# V1.net
KiCad netlist of a schematic drawn in EAGLE
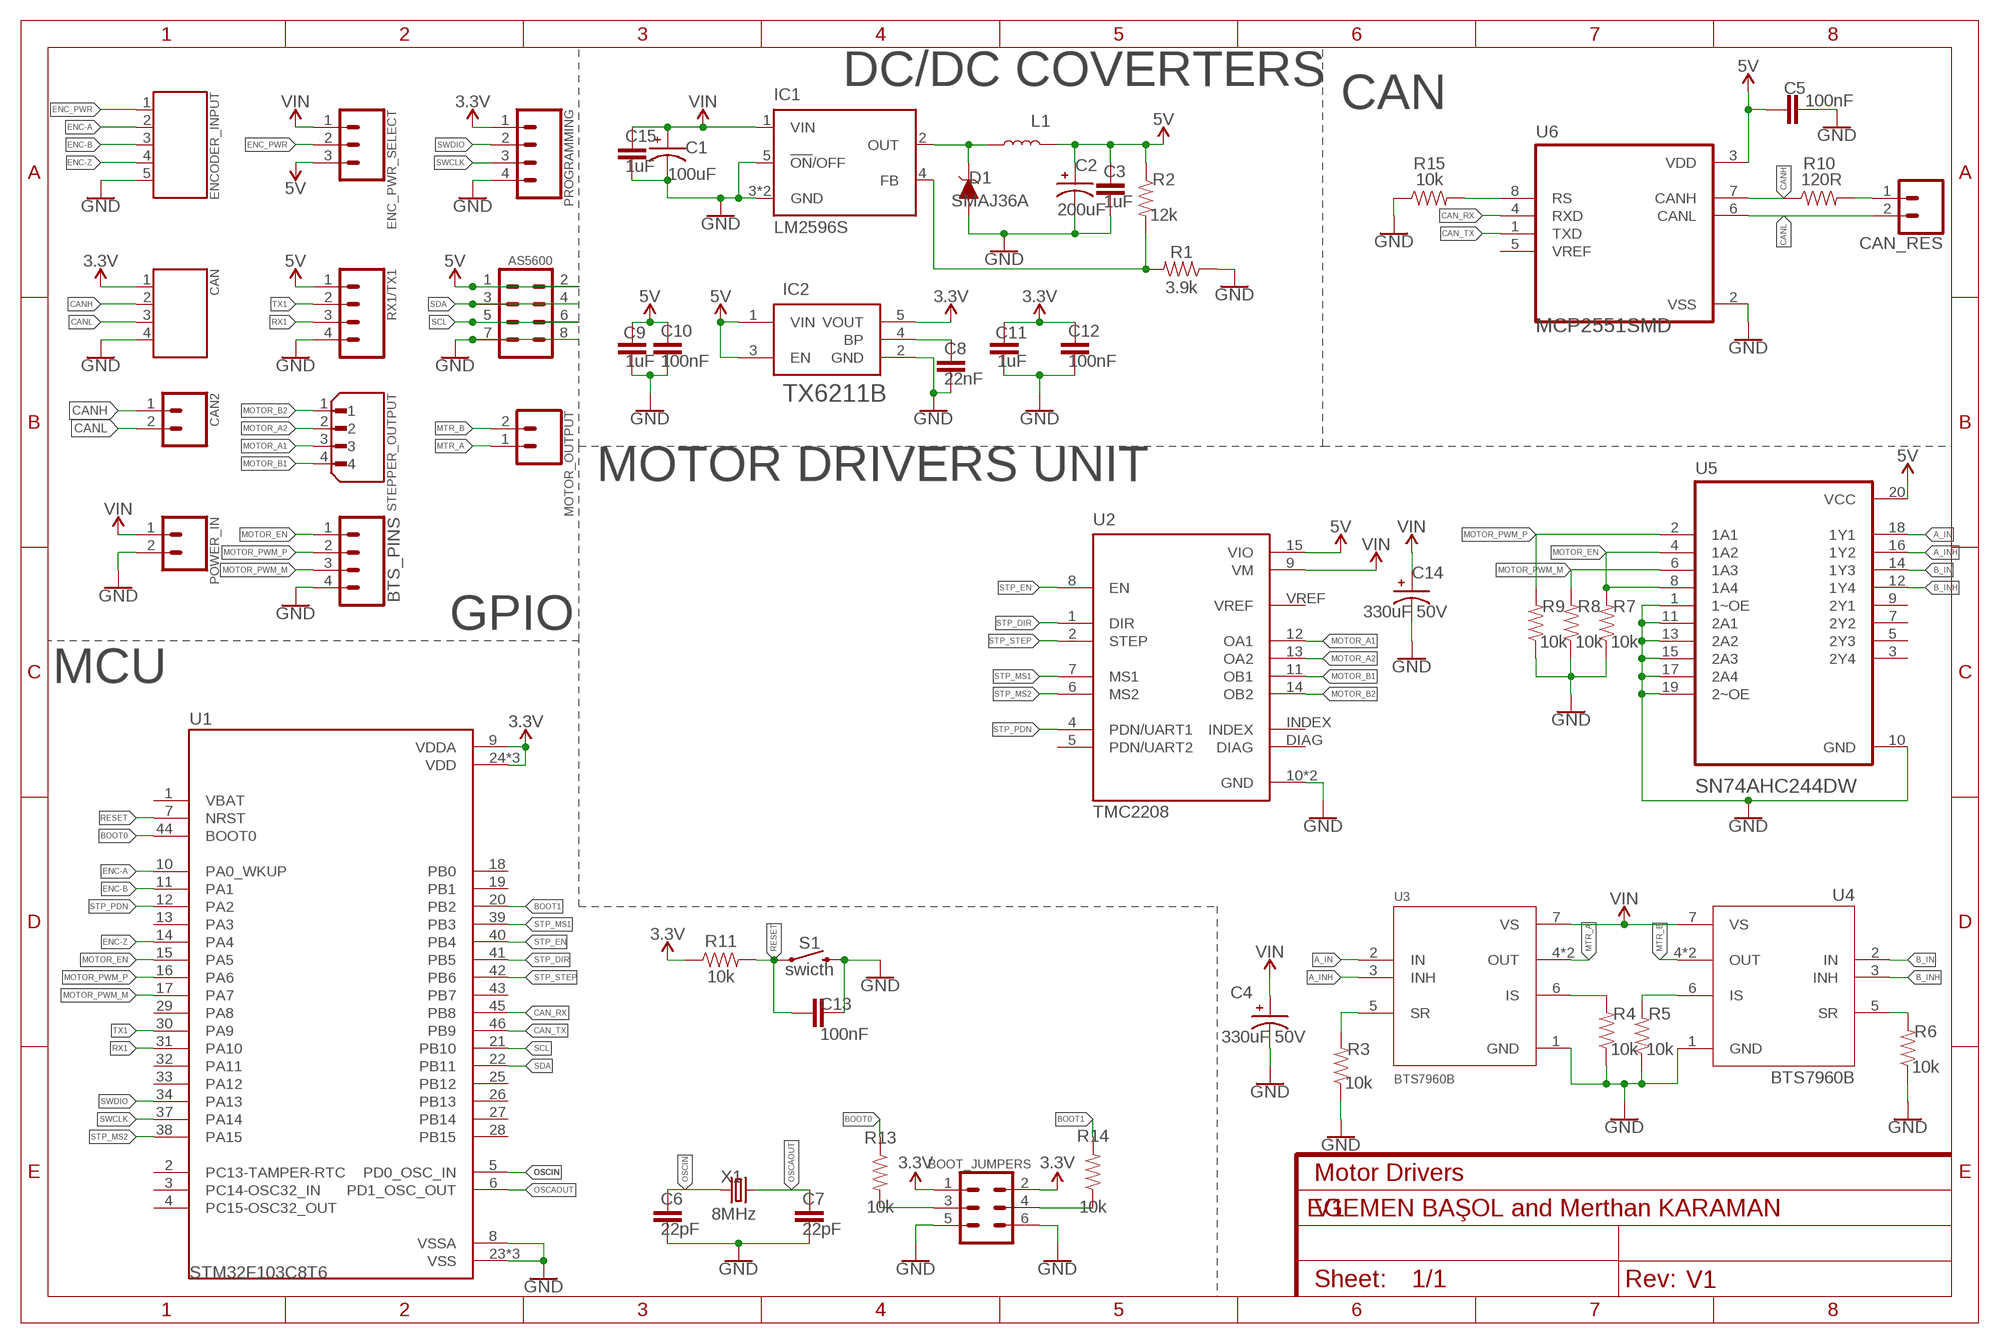
[diagram p0: schematic, sheet 1]

(export (version "E")
  (design (tool "Eeschema 10.0.6"))
  (components
    (comp (ref "AS5600")
      (value "5V/SDA/SCL/GND")
      (footprint "eagle-import:2X4")
      (libsource (lib "eagle-import") (part "CONN_04X2"))
    )
    (comp (ref "BOOT_JUMPERS")
      (value "CONN_03X2FEMALE")
      (footprint "eagle-import:2X3")
      (libsource (lib "eagle-import") (part "CONN_03X2FEMALE"))
    )
    (comp (ref "BTS_PINS")
      (value "GND/ PWM_M/ PWM_P/ EN")
      (footprint "eagle-import:1X04")
      (libsource (lib "eagle-import") (part "CONN_04"))
    )
    (comp (ref "C1")
      (value "100uF")
      (footprint "eagle-import:CPOL-SMD")
      (fields (field (name "MF") "Panasonic") (field (name "MP") "EEEFN1H101L"))
      (libsource (lib "eagle-import") (part "CPOL-SMD"))
    )
    (comp (ref "C2")
      (value "200uF")
      (footprint "eagle-import:CPOL-SMD")
      (fields (field (name "MF") "Panasonic") (field (name "MP") "EEEFN1H101L"))
      (libsource (lib "eagle-import") (part "CPOL-SMD"))
    )
    (comp (ref "C3")
      (value "1uF")
      (footprint "eagle-import:0603")
      (libsource (lib "eagle-import") (part "0.18UF-0603-10V-10%"))
    )
    (comp (ref "C4")
      (value "330uF 50V")
      (footprint "eagle-import:CPOL-RADIAL-5MM-10MM")
      (fields (field (name "MF") "Panasonic") (field (name "MP") "ECA2VM4R7"))
      (libsource (lib "eagle-import") (part "CPOL-RADIAL-5MM-10MM"))
    )
    (comp (ref "C5")
      (value "100nF")
      (footprint "eagle-import:0805")
      (libsource (lib "eagle-import") (part "CAP-0805"))
    )
    (comp (ref "C6")
      (value "22pF")
      (footprint "eagle-import:0805")
      (libsource (lib "eagle-import") (part "2.2UF-0805-25V-(+80/-20%)"))
    )
    (comp (ref "C7")
      (value "22pF")
      (footprint "eagle-import:0805")
      (libsource (lib "eagle-import") (part "2.2UF-0805-25V-(+80/-20%)"))
    )
    (comp (ref "C8")
      (value "22nF")
      (footprint "eagle-import:0805")
      (libsource (lib "eagle-import") (part "2.2UF-0805-25V-(+80/-20%)"))
    )
    (comp (ref "C9")
      (value "1uF")
      (footprint "eagle-import:0805")
      (libsource (lib "eagle-import") (part "CAP-0805"))
    )
    (comp (ref "C10")
      (value "100nF")
      (footprint "eagle-import:0805")
      (libsource (lib "eagle-import") (part "2.2UF-0805-25V-(+80/-20%)"))
    )
    (comp (ref "C11")
      (value "1uF")
      (footprint "eagle-import:0805")
      (libsource (lib "eagle-import") (part "CAP-0805"))
    )
    (comp (ref "C12")
      (value "100nF")
      (footprint "eagle-import:0805")
      (libsource (lib "eagle-import") (part "2.2UF-0805-25V-(+80/-20%)"))
    )
    (comp (ref "C13")
      (value "100nF")
      (footprint "eagle-import:0805")
      (libsource (lib "eagle-import") (part "2.2UF-0805-25V-(+80/-20%)"))
    )
    (comp (ref "C14")
      (value "330uF 50V")
      (footprint "eagle-import:CPOL-RADIAL-5MM-10MM")
      (fields (field (name "MF") "Panasonic") (field (name "MP") "ECA2VM4R7"))
      (libsource (lib "eagle-import") (part "CPOL-RADIAL-5MM-10MM"))
    )
    (comp (ref "C15")
      (value "1uF")
      (footprint "eagle-import:0805")
      (libsource (lib "eagle-import") (part "2.2UF-0805-25V-(+80/-20%)"))
    )
    (comp (ref "CAN")
      (value "3.3V/CANH/CANL/GND")
      (footprint "eagle-import:5.08MM_4PIN")
      (fields (field (name "MF") "CUI Devices") (field (name "MP") "TB006-508-04BE"))
      (libsource (lib "eagle-import") (part "5.08MM_4PIN"))
    )
    (comp (ref "CAN2")
      (value "CANH/CANL")
      (footprint "eagle-import:5.08MM_2PIN")
      (libsource (lib "eagle-import") (part "5.08MM_2PIN"))
    )
    (comp (ref "CAN_RES")
      (value "CONN_02")
      (footprint "eagle-import:1X02")
      (libsource (lib "eagle-import") (part "CONN_02"))
    )
    (comp (ref "D1")
      (value "SMAJ36A")
      (footprint "eagle-import:DO-214AC")
      (libsource (lib "eagle-import") (part "DIODE_TVS_UNI"))
    )
    (comp (ref "ENCODER_INPUT")
      (value "PWR/A/B/Z/GND")
      (footprint "eagle-import:5.08MM_5PIN")
      (fields (field (name "MF") "CUI Devices") (field (name "MP") "TB006-508-05BE"))
      (libsource (lib "eagle-import") (part "5.08MM_5PIN"))
    )
    (comp (ref "ENC_PWR_SELECT")
      (value "VIN/PWR/5V")
      (footprint "eagle-import:1X03")
      (libsource (lib "eagle-import") (part "CONN_03"))
    )
    (comp (ref "IC1")
      (value "LM2596S")
      (footprint "eagle-import:TO263-5")
      (libsource (lib "eagle-import") (part "LM2596S"))
    )
    (comp (ref "IC2")
      (value "TX6211B")
      (footprint "eagle-import:SOT23-5")
      (libsource (lib "eagle-import") (part "TX6211B"))
    )
    (comp (ref "L1")
      (value "47uH")
      (footprint "eagle-import:COIL_14X14")
      (libsource (lib "eagle-import") (part "COIL"))
    )
    (comp (ref "MOTOR_OUTPUT")
      (value "5.08MM_2PIN")
      (footprint "eagle-import:5.08MM_2PIN")
      (libsource (lib "eagle-import") (part "5.08MM_2PIN"))
    )
    (comp (ref "POWER_IN")
      (value "VIN/GND")
      (footprint "eagle-import:5.08MM_2PIN")
      (libsource (lib "eagle-import") (part "5.08MM_2PIN"))
    )
    (comp (ref "PROGRAMMING")
      (value "3.3V/SWDIO/SWCLK/GND")
      (footprint "eagle-import:1X04")
      (libsource (lib "eagle-import") (part "CONN_04"))
    )
    (comp (ref "R1")
      (value "3.9k")
      (footprint "eagle-import:0805")
      (libsource (lib "eagle-import") (part "RESISTOR0805"))
    )
    (comp (ref "R2")
      (value "12k")
      (footprint "eagle-import:0805")
      (libsource (lib "eagle-import") (part "RESISTOR0805"))
    )
    (comp (ref "R3")
      (value "10k")
      (footprint "eagle-import:0805")
      (libsource (lib "eagle-import") (part "RESISTOR0805"))
    )
    (comp (ref "R4")
      (value "10k")
      (footprint "eagle-import:0805")
      (libsource (lib "eagle-import") (part "RESISTOR0805"))
    )
    (comp (ref "R5")
      (value "10k")
      (footprint "eagle-import:0805")
      (libsource (lib "eagle-import") (part "RESISTOR0805"))
    )
    (comp (ref "R6")
      (value "10k")
      (footprint "eagle-import:0805")
      (libsource (lib "eagle-import") (part "RESISTOR0805"))
    )
    (comp (ref "R7")
      (value "10k")
      (footprint "eagle-import:0805")
      (libsource (lib "eagle-import") (part "RESISTOR0805"))
    )
    (comp (ref "R8")
      (value "10k")
      (footprint "eagle-import:0805")
      (libsource (lib "eagle-import") (part "RESISTOR0805"))
    )
    (comp (ref "R9")
      (value "10k")
      (footprint "eagle-import:0805")
      (libsource (lib "eagle-import") (part "RESISTOR0805"))
    )
    (comp (ref "R10")
      (value "120R")
      (footprint "eagle-import:0805")
      (libsource (lib "eagle-import") (part "RESISTOR0805"))
    )
    (comp (ref "R11")
      (value "10k")
      (footprint "eagle-import:0805")
      (libsource (lib "eagle-import") (part "SparkFun-Resistors_532_RESISTOR0805"))
    )
    (comp (ref "R13")
      (value "10k")
      (footprint "eagle-import:0805")
      (libsource (lib "eagle-import") (part "SparkFun-Resistors_532_RESISTOR0805"))
    )
    (comp (ref "R14")
      (value "10k")
      (footprint "eagle-import:0805")
      (libsource (lib "eagle-import") (part "SparkFun-Resistors_532_RESISTOR0805"))
    )
    (comp (ref "R15")
      (value "10k")
      (footprint "eagle-import:0805")
      (libsource (lib "eagle-import") (part "RESISTOR0805"))
    )
    (comp (ref "RX1/TX1")
      (value "5V/TX1/RX1/GND")
      (footprint "eagle-import:1X04")
      (libsource (lib "eagle-import") (part "CONN_04"))
    )
    (comp (ref "S1")
      (value "swicth")
      (footprint "eagle-import:TACTILE_SWITCH_SMD_5.2MM")
      (libsource (lib "eagle-import") (part "MOMENTARY-SWITCH-SPST-SMD-5.2MM-TALL"))
    )
    (comp (ref "STEPPER_OUTPUT")
      (value "4PIN_TUNIC_2.5MM")
      (footprint "eagle-import:JST_B4B-XH-A(LF)(SN)")
      (fields (field (name "MF") "JST Sales") (field (name "MP") "B4B-XH-A(LF)(SN)"))
      (libsource (lib "eagle-import") (part "4PIN_TUNIC_2.5MM"))
    )
    (comp (ref "U1")
      (value "STM32F103C8T6")
      (footprint "eagle-import:LQFP-48")
      (fields (field (name "MF") "STMicroelectronics"))
      (libsource (lib "eagle-import") (part "STM32F103C8T6"))
    )
    (comp (ref "U2")
      (value "TMC2208")
      (footprint "eagle-import:MODULE_TMC2208_SILENTSTEPSTICK")
      (fields (field (name "MF") "Trinamic Motion") (field (name "MP") "TMC2208 SILENTSTEPSTICK"))
      (libsource (lib "eagle-import") (part "TMC2208_SILENTSTEPSTICK"))
    )
    (comp (ref "U3")
      (value "BTS7960B")
      (footprint "eagle-import:DPAK127P1490X440-8N")
      (libsource (lib "eagle-import") (part "BTS7960B"))
    )
    (comp (ref "U4")
      (value "BTS7960B")
      (footprint "eagle-import:DPAK127P1490X440-8N")
      (libsource (lib "eagle-import") (part "BTS7960B"))
    )
    (comp (ref "U5")
      (value "SN74AHC244DW")
      (footprint "eagle-import:SOIC127P1030X265-20N")
      (fields (field (name "MF") "Texas Instruments"))
      (libsource (lib "eagle-import") (part "SN74AHC244DW"))
    )
    (comp (ref "U6")
      (value "MCP2551SMD")
      (footprint "eagle-import:SOIC-8")
      (libsource (lib "eagle-import") (part "MCP2551SMD"))
    )
    (comp (ref "X1")
      (value "8MHz")
      (footprint "eagle-import:HC49")
      (libsource (lib "eagle-import") (part "CRYSTALS-NOGND-HC49"))
    )
  )
  (nets
    (net (code "1") (name "3.3V") (class "Default")
      (node (ref "BOOT_JUMPERS") (pin "1") (pinfunction "1_1") (pintype "bidirectional"))
      (node (ref "BOOT_JUMPERS") (pin "2") (pinfunction "2_2") (pintype "bidirectional"))
      (node (ref "C11") (pin "2") (pinfunction "2_2") (pintype "passive"))
      (node (ref "C12") (pin "2") (pinfunction "2_2") (pintype "passive"))
      (node (ref "CAN") (pin "1") (pinfunction "1_1") (pintype "passive"))
      (node (ref "IC2") (pin "5") (pinfunction "VOUT_5") (pintype "output"))
      (node (ref "PROGRAMMING") (pin "1") (pinfunction "1_1") (pintype "passive"))
      (node (ref "R11") (pin "1") (pinfunction "1_1") (pintype "passive"))
      (node (ref "U1") (pin "24") (pinfunction "VDD_24") (pintype "power_in"))
      (node (ref "U1") (pin "36") (pinfunction "VDD_36") (pintype "power_in"))
      (node (ref "U1") (pin "48") (pinfunction "VDD_48") (pintype "power_in"))
      (node (ref "U1") (pin "9") (pinfunction "VDDA_9") (pintype "power_in"))
    )
    (net (code "2") (name "5V") (class "Default")
      (node (ref "AS5600") (pin "1") (pinfunction "1_1") (pintype "passive"))
      (node (ref "AS5600") (pin "2") (pinfunction "2_2") (pintype "passive"))
      (node (ref "C10") (pin "2") (pinfunction "2_2") (pintype "passive"))
      (node (ref "C2") (pin "1") (pinfunction "1_1") (pintype "passive"))
      (node (ref "C3") (pin "2") (pinfunction "2_2") (pintype "passive"))
      (node (ref "C5") (pin "2") (pinfunction "2_2") (pintype "passive"))
      (node (ref "C9") (pin "2") (pinfunction "2_2") (pintype "passive"))
      (node (ref "ENC_PWR_SELECT") (pin "3") (pinfunction "3_3") (pintype "passive"))
      (node (ref "IC2") (pin "1") (pinfunction "VIN_1") (pintype "input"))
      (node (ref "IC2") (pin "3") (pinfunction "EN_3") (pintype "input"))
      (node (ref "L1") (pin "P$2") (pinfunction "2_P$2") (pintype "passive"))
      (node (ref "R2") (pin "1") (pinfunction "1_1") (pintype "passive"))
      (node (ref "RX1/TX1") (pin "1") (pinfunction "1_1") (pintype "passive"))
      (node (ref "U2") (pin "15") (pinfunction "VIO_15") (pintype "power_in"))
      (node (ref "U5") (pin "20") (pinfunction "VCC_20") (pintype "power_in"))
      (node (ref "U6") (pin "3") (pinfunction "VDD_3") (pintype "power_in"))
    )
    (net (code "3") (name "A_IN") (class "Default")
      (node (ref "U3") (pin "2") (pinfunction "IN_2") (pintype "input"))
      (node (ref "U5") (pin "18") (pinfunction "1Y1_18") (pintype "output"))
    )
    (net (code "4") (name "A_INH") (class "Default")
      (node (ref "U3") (pin "3") (pinfunction "INH_3") (pintype "input"))
      (node (ref "U5") (pin "16") (pinfunction "1Y2_16") (pintype "output"))
    )
    (net (code "5") (name "BOOT0") (class "Default")
      (node (ref "R13") (pin "1") (pinfunction "1_1") (pintype "passive"))
      (node (ref "U1") (pin "44") (pinfunction "BOOT0_44") (pintype "input"))
    )
    (net (code "6") (name "BOOT1") (class "Default")
      (node (ref "R14") (pin "2") (pinfunction "2_2") (pintype "passive"))
      (node (ref "U1") (pin "20") (pinfunction "PB2_20") (pintype "bidirectional"))
    )
    (net (code "7") (name "B_IN") (class "Default")
      (node (ref "U4") (pin "2") (pinfunction "IN_2") (pintype "input"))
      (node (ref "U5") (pin "14") (pinfunction "1Y3_14") (pintype "output"))
    )
    (net (code "8") (name "B_INH") (class "Default")
      (node (ref "U4") (pin "3") (pinfunction "INH_3") (pintype "input"))
      (node (ref "U5") (pin "12") (pinfunction "1Y4_12") (pintype "output"))
    )
    (net (code "9") (name "CANH") (class "Default")
      (node (ref "CAN") (pin "2") (pinfunction "2_2") (pintype "passive"))
      (node (ref "CAN2") (pin "1") (pinfunction "1_1") (pintype "passive"))
      (node (ref "R10") (pin "1") (pinfunction "1_1") (pintype "passive"))
      (node (ref "U6") (pin "7") (pinfunction "CANH_7") (pintype "output"))
    )
    (net (code "10") (name "CANL") (class "Default")
      (node (ref "CAN") (pin "3") (pinfunction "3_3") (pintype "passive"))
      (node (ref "CAN2") (pin "2") (pinfunction "2_2") (pintype "passive"))
      (node (ref "CAN_RES") (pin "2") (pinfunction "2_2") (pintype "passive"))
      (node (ref "U6") (pin "6") (pinfunction "CANL_6") (pintype "output"))
    )
    (net (code "11") (name "CAN_RX") (class "Default")
      (node (ref "U1") (pin "45") (pinfunction "PB8_45") (pintype "bidirectional"))
      (node (ref "U6") (pin "4") (pinfunction "RXD_4") (pintype "input"))
    )
    (net (code "12") (name "CAN_TX") (class "Default")
      (node (ref "U1") (pin "46") (pinfunction "PB9_46") (pintype "bidirectional"))
      (node (ref "U6") (pin "1") (pinfunction "TXD_1") (pintype "input"))
    )
    (net (code "13") (name "ENC-A") (class "Default")
      (node (ref "ENCODER_INPUT") (pin "2") (pinfunction "2_2") (pintype "passive"))
      (node (ref "U1") (pin "10") (pinfunction "PA0_WKUP_10") (pintype "bidirectional"))
    )
    (net (code "14") (name "ENC-B") (class "Default")
      (node (ref "ENCODER_INPUT") (pin "3") (pinfunction "3_3") (pintype "passive"))
      (node (ref "U1") (pin "11") (pinfunction "PA1_11") (pintype "bidirectional"))
    )
    (net (code "15") (name "ENC-Z") (class "Default")
      (node (ref "ENCODER_INPUT") (pin "4") (pinfunction "4_4") (pintype "passive"))
      (node (ref "U1") (pin "14") (pinfunction "PA4_14") (pintype "bidirectional"))
    )
    (net (code "16") (name "ENC_PWR") (class "Default")
      (node (ref "ENCODER_INPUT") (pin "1") (pinfunction "1_1") (pintype "passive"))
      (node (ref "ENC_PWR_SELECT") (pin "2") (pinfunction "2_2") (pintype "passive"))
    )
    (net (code "17") (name "GND") (class "Default")
      (node (ref "AS5600") (pin "7") (pinfunction "7_7") (pintype "passive"))
      (node (ref "AS5600") (pin "8") (pinfunction "8_8") (pintype "passive"))
      (node (ref "BOOT_JUMPERS") (pin "5") (pinfunction "5_5") (pintype "bidirectional"))
      (node (ref "BOOT_JUMPERS") (pin "6") (pinfunction "6_6") (pintype "bidirectional"))
      (node (ref "BTS_PINS") (pin "4") (pinfunction "4_4") (pintype "passive"))
      (node (ref "C1") (pin "2") (pinfunction "2_2") (pintype "passive"))
      (node (ref "C10") (pin "1") (pinfunction "1_1") (pintype "passive"))
      (node (ref "C11") (pin "1") (pinfunction "1_1") (pintype "passive"))
      (node (ref "C12") (pin "1") (pinfunction "1_1") (pintype "passive"))
      (node (ref "C13") (pin "1") (pinfunction "1_1") (pintype "passive"))
      (node (ref "C14") (pin "N") (pinfunction "N_N") (pintype "passive"))
      (node (ref "C15") (pin "1") (pinfunction "1_1") (pintype "passive"))
      (node (ref "C2") (pin "2") (pinfunction "2_2") (pintype "passive"))
      (node (ref "C3") (pin "1") (pinfunction "1_1") (pintype "passive"))
      (node (ref "C4") (pin "N") (pinfunction "N_N") (pintype "passive"))
      (node (ref "C5") (pin "1") (pinfunction "1_1") (pintype "passive"))
      (node (ref "C6") (pin "1") (pinfunction "1_1") (pintype "passive"))
      (node (ref "C7") (pin "1") (pinfunction "1_1") (pintype "passive"))
      (node (ref "C8") (pin "1") (pinfunction "1_1") (pintype "passive"))
      (node (ref "C9") (pin "1") (pinfunction "1_1") (pintype "passive"))
      (node (ref "CAN") (pin "4") (pinfunction "4_4") (pintype "passive"))
      (node (ref "D1") (pin "A") (pinfunction "A_A") (pintype "passive"))
      (node (ref "ENCODER_INPUT") (pin "5") (pinfunction "5_5") (pintype "passive"))
      (node (ref "IC1") (pin "3") (pinfunction "GND_3") (pintype "power_in"))
      (node (ref "IC1") (pin "5") (pinfunction "~{ON}/OFF_5") (pintype "input"))
      (node (ref "IC1") (pin "TAB") (pinfunction "GND_TAB") (pintype "power_in"))
      (node (ref "IC2") (pin "2") (pinfunction "GND_2") (pintype "power_in"))
      (node (ref "POWER_IN") (pin "2") (pinfunction "2_2") (pintype "passive"))
      (node (ref "PROGRAMMING") (pin "4") (pinfunction "4_4") (pintype "passive"))
      (node (ref "R1") (pin "1") (pinfunction "1_1") (pintype "passive"))
      (node (ref "R15") (pin "1") (pinfunction "1_1") (pintype "passive"))
      (node (ref "R3") (pin "1") (pinfunction "1_1") (pintype "passive"))
      (node (ref "R4") (pin "1") (pinfunction "1_1") (pintype "passive"))
      (node (ref "R5") (pin "1") (pinfunction "1_1") (pintype "passive"))
      (node (ref "R6") (pin "1") (pinfunction "1_1") (pintype "passive"))
      (node (ref "R7") (pin "1") (pinfunction "1_1") (pintype "passive"))
      (node (ref "R8") (pin "1") (pinfunction "1_1") (pintype "passive"))
      (node (ref "R9") (pin "1") (pinfunction "1_1") (pintype "passive"))
      (node (ref "RX1/TX1") (pin "4") (pinfunction "4_4") (pintype "passive"))
      (node (ref "S1") (pin "3") (pinfunction "2_3") (pintype "passive"))
      (node (ref "U1") (pin "23") (pinfunction "VSS_23") (pintype "power_in"))
      (node (ref "U1") (pin "35") (pinfunction "VSS_35") (pintype "power_in"))
      (node (ref "U1") (pin "47") (pinfunction "VSS_47") (pintype "power_in"))
      (node (ref "U1") (pin "8") (pinfunction "VSSA_8") (pintype "power_in"))
      (node (ref "U2") (pin "10") (pinfunction "GND_10") (pintype "power_in"))
      (node (ref "U2") (pin "16") (pinfunction "GND_16") (pintype "power_in"))
      (node (ref "U3") (pin "1") (pinfunction "GND_1") (pintype "power_in"))
      (node (ref "U4") (pin "1") (pinfunction "GND_1") (pintype "power_in"))
      (node (ref "U5") (pin "1") (pinfunction "1~{OE}_1") (pintype "input"))
      (node (ref "U5") (pin "10") (pinfunction "GND_10") (pintype "power_in"))
      (node (ref "U5") (pin "11") (pinfunction "2A1_11") (pintype "input"))
      (node (ref "U5") (pin "13") (pinfunction "2A2_13") (pintype "input"))
      (node (ref "U5") (pin "15") (pinfunction "2A3_15") (pintype "input"))
      (node (ref "U5") (pin "17") (pinfunction "2A4_17") (pintype "input"))
      (node (ref "U5") (pin "19") (pinfunction "2~{OE}_19") (pintype "input"))
      (node (ref "U6") (pin "2") (pinfunction "VSS_2") (pintype "power_in"))
    )
    (net (code "18") (name "MOTOR_A1") (class "Default")
      (node (ref "STEPPER_OUTPUT") (pin "3") (pinfunction "3_3") (pintype "passive"))
      (node (ref "U2") (pin "12") (pinfunction "OA1_12") (pintype "passive"))
    )
    (net (code "19") (name "MOTOR_A2") (class "Default")
      (node (ref "STEPPER_OUTPUT") (pin "2") (pinfunction "2_2") (pintype "passive"))
      (node (ref "U2") (pin "13") (pinfunction "OA2_13") (pintype "passive"))
    )
    (net (code "20") (name "MOTOR_B1") (class "Default")
      (node (ref "STEPPER_OUTPUT") (pin "4") (pinfunction "4_4") (pintype "passive"))
      (node (ref "U2") (pin "11") (pinfunction "OB1_11") (pintype "passive"))
    )
    (net (code "21") (name "MOTOR_B2") (class "Default")
      (node (ref "STEPPER_OUTPUT") (pin "1") (pinfunction "1_1") (pintype "passive"))
      (node (ref "U2") (pin "14") (pinfunction "OB2_14") (pintype "passive"))
    )
    (net (code "22") (name "MOTOR_EN") (class "Default")
      (node (ref "BTS_PINS") (pin "1") (pinfunction "1_1") (pintype "passive"))
      (node (ref "R7") (pin "2") (pinfunction "2_2") (pintype "passive"))
      (node (ref "U1") (pin "15") (pinfunction "PA5_15") (pintype "bidirectional"))
      (node (ref "U5") (pin "4") (pinfunction "1A2_4") (pintype "input"))
      (node (ref "U5") (pin "8") (pinfunction "1A4_8") (pintype "input"))
    )
    (net (code "23") (name "MOTOR_PWM_M") (class "Default")
      (node (ref "BTS_PINS") (pin "3") (pinfunction "3_3") (pintype "passive"))
      (node (ref "R8") (pin "2") (pinfunction "2_2") (pintype "passive"))
      (node (ref "U1") (pin "17") (pinfunction "PA7_17") (pintype "bidirectional"))
      (node (ref "U5") (pin "6") (pinfunction "1A3_6") (pintype "input"))
    )
    (net (code "24") (name "MOTOR_PWM_P") (class "Default")
      (node (ref "BTS_PINS") (pin "2") (pinfunction "2_2") (pintype "passive"))
      (node (ref "R9") (pin "2") (pinfunction "2_2") (pintype "passive"))
      (node (ref "U1") (pin "16") (pinfunction "PA6_16") (pintype "bidirectional"))
      (node (ref "U5") (pin "2") (pinfunction "1A1_2") (pintype "input"))
    )
    (net (code "25") (name "MTR_A") (class "Default")
      (node (ref "MOTOR_OUTPUT") (pin "1") (pinfunction "1_1") (pintype "passive"))
      (node (ref "U3") (pin "4") (pinfunction "OUT_4") (pintype "output"))
      (node (ref "U3") (pin "8") (pinfunction "OUT_8") (pintype "output"))
    )
    (net (code "26") (name "MTR_B") (class "Default")
      (node (ref "MOTOR_OUTPUT") (pin "2") (pinfunction "2_2") (pintype "passive"))
      (node (ref "U4") (pin "4") (pinfunction "OUT_4") (pintype "output"))
      (node (ref "U4") (pin "8") (pinfunction "OUT_8") (pintype "output"))
    )
    (net (code "27") (name "Net-(BOOT_JUMPERS-Pad3)") (class "Default")
      (node (ref "BOOT_JUMPERS") (pin "3") (pinfunction "3_3") (pintype "bidirectional"))
      (node (ref "R13") (pin "2") (pinfunction "2_2") (pintype "passive"))
    )
    (net (code "28") (name "Net-(BOOT_JUMPERS-Pad4)") (class "Default")
      (node (ref "BOOT_JUMPERS") (pin "4") (pinfunction "4_4") (pintype "bidirectional"))
      (node (ref "R14") (pin "1") (pinfunction "1_1") (pintype "passive"))
    )
    (net (code "29") (name "Net-(CAN_RES-Pad1)") (class "Default")
      (node (ref "CAN_RES") (pin "1") (pinfunction "1_1") (pintype "passive"))
      (node (ref "R10") (pin "2") (pinfunction "2_2") (pintype "passive"))
    )
    (net (code "30") (name "Net-(IC1-FB)") (class "Default")
      (node (ref "IC1") (pin "4") (pinfunction "FB_4") (pintype "input"))
      (node (ref "R1") (pin "2") (pinfunction "2_2") (pintype "passive"))
      (node (ref "R2") (pin "2") (pinfunction "2_2") (pintype "passive"))
    )
    (net (code "31") (name "Net-(IC1-OUT)") (class "Default")
      (node (ref "D1") (pin "C") (pinfunction "C_C") (pintype "passive"))
      (node (ref "IC1") (pin "2") (pinfunction "OUT_2") (pintype "output"))
      (node (ref "L1") (pin "P$1") (pinfunction "1_P$1") (pintype "passive"))
    )
    (net (code "32") (name "Net-(IC2-BP)") (class "Default")
      (node (ref "C8") (pin "2") (pinfunction "2_2") (pintype "passive"))
      (node (ref "IC2") (pin "4") (pinfunction "BP_4") (pintype "passive"))
    )
    (net (code "33") (name "Net-(U3-IS)") (class "Default")
      (node (ref "R4") (pin "2") (pinfunction "2_2") (pintype "passive"))
      (node (ref "U3") (pin "6") (pinfunction "IS_6") (pintype "output"))
    )
    (net (code "34") (name "Net-(U3-SR)") (class "Default")
      (node (ref "R3") (pin "2") (pinfunction "2_2") (pintype "passive"))
      (node (ref "U3") (pin "5") (pinfunction "SR_5") (pintype "input"))
    )
    (net (code "35") (name "Net-(U4-IS)") (class "Default")
      (node (ref "R5") (pin "2") (pinfunction "2_2") (pintype "passive"))
      (node (ref "U4") (pin "6") (pinfunction "IS_6") (pintype "output"))
    )
    (net (code "36") (name "Net-(U4-SR)") (class "Default")
      (node (ref "R6") (pin "2") (pinfunction "2_2") (pintype "passive"))
      (node (ref "U4") (pin "5") (pinfunction "SR_5") (pintype "input"))
    )
    (net (code "37") (name "Net-(U6-RS)") (class "Default")
      (node (ref "R15") (pin "2") (pinfunction "2_2") (pintype "passive"))
      (node (ref "U6") (pin "8") (pinfunction "RS_8") (pintype "input"))
    )
    (net (code "38") (name "OSCAOUT") (class "Default")
      (node (ref "C7") (pin "2") (pinfunction "2_2") (pintype "passive"))
      (node (ref "U1") (pin "6") (pinfunction "PD1_OSC_OUT_6") (pintype "bidirectional"))
      (node (ref "X1") (pin "2") (pinfunction "2_2") (pintype "passive"))
    )
    (net (code "39") (name "OSCIN") (class "Default")
      (node (ref "C6") (pin "2") (pinfunction "2_2") (pintype "passive"))
      (node (ref "U1") (pin "5") (pinfunction "PD0_OSC_IN_5") (pintype "bidirectional"))
      (node (ref "X1") (pin "1") (pinfunction "1_1") (pintype "passive"))
    )
    (net (code "40") (name "RESET") (class "Default")
      (node (ref "C13") (pin "2") (pinfunction "2_2") (pintype "passive"))
      (node (ref "R11") (pin "2") (pinfunction "2_2") (pintype "passive"))
      (node (ref "S1") (pin "1") (pinfunction "1_1") (pintype "passive"))
      (node (ref "U1") (pin "7") (pinfunction "NRST_7") (pintype "input"))
    )
    (net (code "41") (name "RX1") (class "Default")
      (node (ref "RX1/TX1") (pin "3") (pinfunction "3_3") (pintype "passive"))
      (node (ref "U1") (pin "31") (pinfunction "PA10_31") (pintype "bidirectional"))
    )
    (net (code "42") (name "SCL") (class "Default")
      (node (ref "AS5600") (pin "5") (pinfunction "5_5") (pintype "passive"))
      (node (ref "AS5600") (pin "6") (pinfunction "6_6") (pintype "passive"))
      (node (ref "U1") (pin "21") (pinfunction "PB10_21") (pintype "bidirectional"))
    )
    (net (code "43") (name "SDA") (class "Default")
      (node (ref "AS5600") (pin "3") (pinfunction "3_3") (pintype "passive"))
      (node (ref "AS5600") (pin "4") (pinfunction "4_4") (pintype "passive"))
      (node (ref "U1") (pin "22") (pinfunction "PB11_22") (pintype "bidirectional"))
    )
    (net (code "44") (name "STP_DIR") (class "Default")
      (node (ref "U1") (pin "41") (pinfunction "PB5_41") (pintype "bidirectional"))
      (node (ref "U2") (pin "1") (pinfunction "DIR_1") (pintype "input"))
    )
    (net (code "45") (name "STP_EN") (class "Default")
      (node (ref "U1") (pin "40") (pinfunction "PB4_40") (pintype "bidirectional"))
      (node (ref "U2") (pin "8") (pinfunction "EN_8") (pintype "input"))
    )
    (net (code "46") (name "STP_MS1") (class "Default")
      (node (ref "U1") (pin "39") (pinfunction "PB3_39") (pintype "bidirectional"))
      (node (ref "U2") (pin "7") (pinfunction "MS1_7") (pintype "input"))
    )
    (net (code "47") (name "STP_MS2") (class "Default")
      (node (ref "U1") (pin "38") (pinfunction "PA15_38") (pintype "bidirectional"))
      (node (ref "U2") (pin "6") (pinfunction "MS2_6") (pintype "input"))
    )
    (net (code "48") (name "STP_PDN") (class "Default")
      (node (ref "U1") (pin "12") (pinfunction "PA2_12") (pintype "bidirectional"))
      (node (ref "U2") (pin "4") (pinfunction "PDN/UART1_4") (pintype "bidirectional"))
    )
    (net (code "49") (name "STP_STEP") (class "Default")
      (node (ref "U1") (pin "42") (pinfunction "PB6_42") (pintype "bidirectional"))
      (node (ref "U2") (pin "2") (pinfunction "STEP_2") (pintype "input"))
    )
    (net (code "50") (name "SWCLK") (class "Default")
      (node (ref "PROGRAMMING") (pin "3") (pinfunction "3_3") (pintype "passive"))
      (node (ref "U1") (pin "37") (pinfunction "PA14_37") (pintype "bidirectional"))
    )
    (net (code "51") (name "SWDIO") (class "Default")
      (node (ref "PROGRAMMING") (pin "2") (pinfunction "2_2") (pintype "passive"))
      (node (ref "U1") (pin "34") (pinfunction "PA13_34") (pintype "bidirectional"))
    )
    (net (code "52") (name "TX1") (class "Default")
      (node (ref "RX1/TX1") (pin "2") (pinfunction "2_2") (pintype "passive"))
      (node (ref "U1") (pin "30") (pinfunction "PA9_30") (pintype "bidirectional"))
    )
    (net (code "53") (name "VIN") (class "Default")
      (node (ref "C1") (pin "1") (pinfunction "1_1") (pintype "passive"))
      (node (ref "C14") (pin "P") (pinfunction "P_P") (pintype "passive"))
      (node (ref "C15") (pin "2") (pinfunction "2_2") (pintype "passive"))
      (node (ref "C4") (pin "P") (pinfunction "P_P") (pintype "passive"))
      (node (ref "ENC_PWR_SELECT") (pin "1") (pinfunction "1_1") (pintype "passive"))
      (node (ref "IC1") (pin "1") (pinfunction "VIN_1") (pintype "input"))
      (node (ref "POWER_IN") (pin "1") (pinfunction "1_1") (pintype "passive"))
      (node (ref "U2") (pin "9") (pinfunction "VM_9") (pintype "power_in"))
      (node (ref "U3") (pin "7") (pinfunction "VS_7") (pintype "power_in"))
      (node (ref "U4") (pin "7") (pinfunction "VS_7") (pintype "power_in"))
    )
    (net (code "54") (name "unconnected-(U1-PA3-Pad13)") (class "Default")
      (node (ref "U1") (pin "13") (pinfunction "PA3_13") (pintype "bidirectional"))
    )
    (net (code "55") (name "unconnected-(U1-PA8-Pad29)") (class "Default")
      (node (ref "U1") (pin "29") (pinfunction "PA8_29") (pintype "bidirectional"))
    )
    (net (code "56") (name "unconnected-(U1-PA11-Pad32)") (class "Default")
      (node (ref "U1") (pin "32") (pinfunction "PA11_32") (pintype "bidirectional"))
    )
    (net (code "57") (name "unconnected-(U1-PA12-Pad33)") (class "Default")
      (node (ref "U1") (pin "33") (pinfunction "PA12_33") (pintype "bidirectional"))
    )
    (net (code "58") (name "unconnected-(U1-PB0-Pad18)") (class "Default")
      (node (ref "U1") (pin "18") (pinfunction "PB0_18") (pintype "bidirectional"))
    )
    (net (code "59") (name "unconnected-(U1-PB1-Pad19)") (class "Default")
      (node (ref "U1") (pin "19") (pinfunction "PB1_19") (pintype "bidirectional"))
    )
    (net (code "60") (name "unconnected-(U1-PB7-Pad43)") (class "Default")
      (node (ref "U1") (pin "43") (pinfunction "PB7_43") (pintype "bidirectional"))
    )
    (net (code "61") (name "unconnected-(U1-PB12-Pad25)") (class "Default")
      (node (ref "U1") (pin "25") (pinfunction "PB12_25") (pintype "bidirectional"))
    )
    (net (code "62") (name "unconnected-(U1-PB13-Pad26)") (class "Default")
      (node (ref "U1") (pin "26") (pinfunction "PB13_26") (pintype "bidirectional"))
    )
    (net (code "63") (name "unconnected-(U1-PB14-Pad27)") (class "Default")
      (node (ref "U1") (pin "27") (pinfunction "PB14_27") (pintype "bidirectional"))
    )
    (net (code "64") (name "unconnected-(U1-PB15-Pad28)") (class "Default")
      (node (ref "U1") (pin "28") (pinfunction "PB15_28") (pintype "bidirectional"))
    )
    (net (code "65") (name "unconnected-(U1-PC13-TAMPER-RTC-Pad2)") (class "Default")
      (node (ref "U1") (pin "2") (pinfunction "PC13-TAMPER-RTC_2") (pintype "bidirectional"))
    )
    (net (code "66") (name "unconnected-(U1-PC14-OSC32_IN-Pad3)") (class "Default")
      (node (ref "U1") (pin "3") (pinfunction "PC14-OSC32_IN_3") (pintype "bidirectional"))
    )
    (net (code "67") (name "unconnected-(U1-PC15-OSC32_OUT-Pad4)") (class "Default")
      (node (ref "U1") (pin "4") (pinfunction "PC15-OSC32_OUT_4") (pintype "bidirectional"))
    )
    (net (code "68") (name "unconnected-(U1-VBAT-Pad1)") (class "Default")
      (node (ref "U1") (pin "1") (pinfunction "VBAT_1") (pintype "bidirectional"))
    )
    (net (code "69") (name "unconnected-(U2-PDN{slash}UART2-Pad5)") (class "Default")
      (node (ref "U2") (pin "5") (pinfunction "PDN/UART2_5") (pintype "bidirectional"))
    )
    (net (code "70") (name "unconnected-(U2-PadDIAG)") (class "Default")
      (node (ref "U2") (pin "DIAG") (pinfunction "DIAG_DIAG") (pintype "output"))
    )
    (net (code "71") (name "unconnected-(U2-PadINDEX)") (class "Default")
      (node (ref "U2") (pin "INDEX") (pinfunction "INDEX_INDEX") (pintype "output"))
    )
    (net (code "72") (name "unconnected-(U2-PadVREF)") (class "Default")
      (node (ref "U2") (pin "VREF") (pinfunction "VREF_VREF") (pintype "passive"))
    )
    (net (code "73") (name "unconnected-(U5-2Y1-Pad9)") (class "Default")
      (node (ref "U5") (pin "9") (pinfunction "2Y1_9") (pintype "output"))
    )
    (net (code "74") (name "unconnected-(U5-2Y2-Pad7)") (class "Default")
      (node (ref "U5") (pin "7") (pinfunction "2Y2_7") (pintype "output"))
    )
    (net (code "75") (name "unconnected-(U5-2Y3-Pad5)") (class "Default")
      (node (ref "U5") (pin "5") (pinfunction "2Y3_5") (pintype "output"))
    )
    (net (code "76") (name "unconnected-(U5-2Y4-Pad3)") (class "Default")
      (node (ref "U5") (pin "3") (pinfunction "2Y4_3") (pintype "output"))
    )
    (net (code "77") (name "unconnected-(U6-VREF-Pad5)") (class "Default")
      (node (ref "U6") (pin "5") (pinfunction "VREF_5") (pintype "input"))
    )
  )
)
